# 2seri1_k.net
KiCad netlist of a schematic drawn in EAGLE
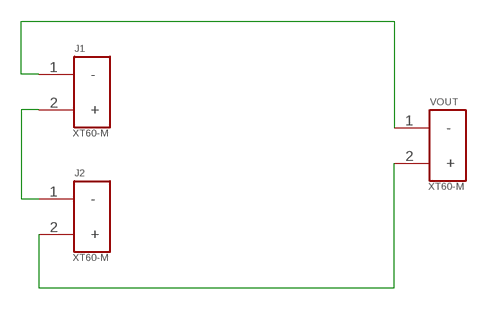
[diagram p0: schematic, sheet 1]

(export (version "E")
  (design (tool "Eeschema 10.0.6"))
  (components
    (comp (ref "J1")
      (value "XT60-M")
      (footprint "eagle-import:AMASS_XT60-M")
      (fields (field (name "MF") "AMASS"))
      (libsource (lib "eagle-import") (part "XT60-M"))
    )
    (comp (ref "J2")
      (value "XT60-M")
      (footprint "eagle-import:AMASS_XT60-M")
      (fields (field (name "MF") "AMASS"))
      (libsource (lib "eagle-import") (part "XT60-M"))
    )
    (comp (ref "VOUT")
      (value "XT60-M")
      (footprint "eagle-import:AMASS_XT60-M")
      (fields (field (name "MF") "AMASS"))
      (libsource (lib "eagle-import") (part "XT60-M"))
    )
  )
  (nets
    (net (code "1") (name "Net-(J1-+)") (class "Default")
      (node (ref "J1") (pin "2") (pinfunction "+_2") (pintype "passive"))
      (node (ref "J2") (pin "1") (pinfunction "-_1") (pintype "passive"))
    )
    (net (code "2") (name "Net-(J1--)") (class "Default")
      (node (ref "J1") (pin "1") (pinfunction "-_1") (pintype "passive"))
      (node (ref "VOUT") (pin "1") (pinfunction "-_1") (pintype "passive"))
    )
    (net (code "3") (name "Net-(J2-+)") (class "Default")
      (node (ref "J2") (pin "2") (pinfunction "+_2") (pintype "passive"))
      (node (ref "VOUT") (pin "2") (pinfunction "+_2") (pintype "passive"))
    )
  )
)
